# Schema_chargeur_USB_projet_robot.net
KiCad netlist of a schematic drawn in Altium Designer
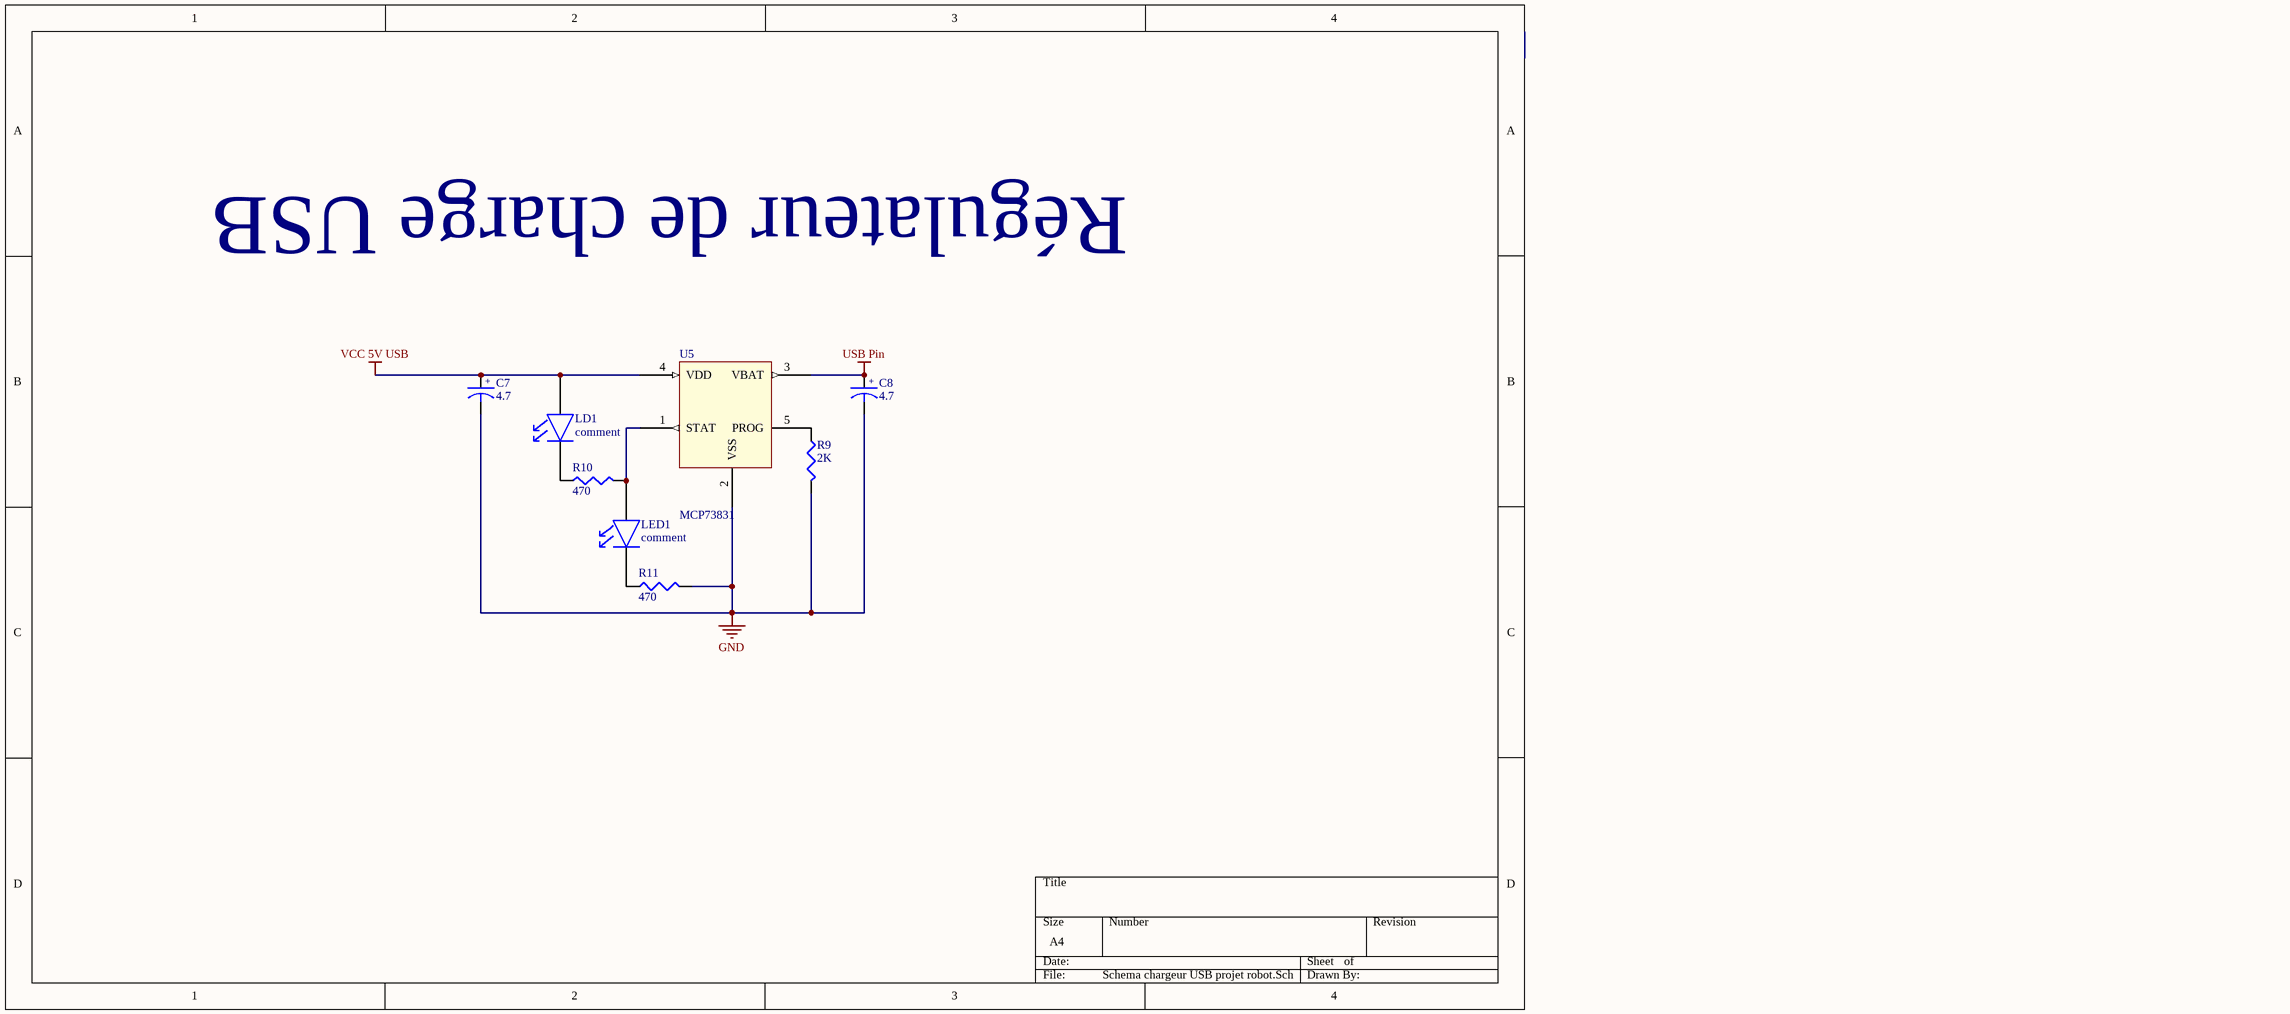
[diagram p0: Schema chargeur USB projet robot.SchDoc]

(export (version "E")
  (design (tool "Eeschema 10.0.6"))
  (components
    (comp (ref "C7")
      (value "4.7")
      (footprint "293D/B")
      (description "capacité polarisée")
      (fields (field (name "Comment") "CAP_POL"))
      (libsource (lib "ISEN_basics_26-05-2015") (part "CAP_POL"))
    )
    (comp (ref "C8")
      (value "4.7")
      (footprint "293D/B")
      (description "capacité polarisée")
      (fields (field (name "Comment") "CAP_POL"))
      (libsource (lib "ISEN_basics_26-05-2015") (part "CAP_POL"))
    )
    (comp (ref "LD1")
      (value "comment")
      (footprint "LED0805")
      (description "LED 5mm/3mm/CMS")
      (libsource (lib "ISEN_basics_26-05-2015") (part "LED"))
    )
    (comp (ref "LED1")
      (value "comment")
      (footprint "LED0805")
      (description "LED 5mm/3mm/CMS")
      (libsource (lib "ISEN_basics_26-05-2015") (part "LED"))
    )
    (comp (ref "R9")
      (value "2K")
      (footprint "0805")
      (description "resistance")
      (fields (field (name "Comment") "RES"))
      (libsource (lib "ISEN_basics_26-05-2015") (part "RES"))
    )
    (comp (ref "R10")
      (value "470")
      (footprint "0805")
      (description "resistance")
      (fields (field (name "Comment") "RES"))
      (libsource (lib "ISEN_basics_26-05-2015") (part "RES"))
    )
    (comp (ref "R11")
      (value "470")
      (footprint "0805")
      (description "resistance")
      (fields (field (name "Comment") "RES"))
      (libsource (lib "ISEN_basics_26-05-2015") (part "RES"))
    )
    (comp (ref "U5")
      (value "MCP73831")
      (footprint "MCP73831")
      (description "Voltage regulator for Li-po or li-ion battery, USB compatible")
      (libsource (lib "MCP73831 Schematic") (part "MCP73831"))
    )
  )
  (nets
    (net (code "1") (name "GND") (class "Default")
      (node (ref "C7") (pin "2") (pinfunction "2_2") (pintype "passive"))
      (node (ref "C8") (pin "2") (pinfunction "2_2") (pintype "passive"))
      (node (ref "R11") (pin "2") (pintype "passive"))
      (node (ref "R9") (pin "2") (pintype "passive"))
      (node (ref "U5") (pin "2") (pinfunction "VSS_2") (pintype "power_in"))
    )
    (net (code "2") (name "Net-(LD1-10)") (class "Default")
      (node (ref "LD1") (pin "K") (pinfunction "10_K") (pintype "passive"))
      (node (ref "R10") (pin "1") (pintype "passive"))
    )
    (net (code "3") (name "Net-(LED1-8)") (class "Default")
      (node (ref "LED1") (pin "A") (pinfunction "8_A") (pintype "passive"))
      (node (ref "R10") (pin "2") (pintype "passive"))
      (node (ref "U5") (pin "1") (pinfunction "STAT_1") (pintype "output"))
    )
    (net (code "4") (name "Net-(LED1-10)") (class "Default")
      (node (ref "LED1") (pin "K") (pinfunction "10_K") (pintype "passive"))
      (node (ref "R11") (pin "1") (pintype "passive"))
    )
    (net (code "5") (name "Net-(U5-PROG)") (class "Default")
      (node (ref "R9") (pin "1") (pintype "passive"))
      (node (ref "U5") (pin "5") (pinfunction "PROG_5") (pintype "power_in"))
    )
    (net (code "6") (name "USB Pin") (class "Default")
      (node (ref "C8") (pin "1") (pinfunction "1_1") (pintype "passive"))
      (node (ref "U5") (pin "3") (pinfunction "VBAT_3") (pintype "output"))
    )
    (net (code "7") (name "VCC 5V USB") (class "Default")
      (node (ref "C7") (pin "1") (pinfunction "1_1") (pintype "passive"))
      (node (ref "LD1") (pin "A") (pinfunction "8_A") (pintype "passive"))
      (node (ref "U5") (pin "4") (pinfunction "VDD_4") (pintype "input"))
    )
  )
)
